# Vss.net
KiCad netlist of a schematic drawn in Altium Designer
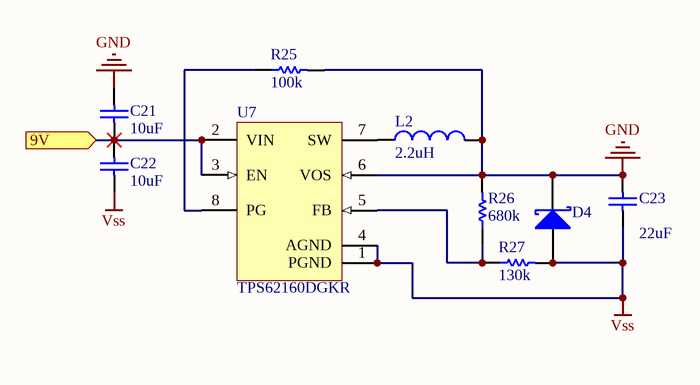
[diagram p0: Vss.SchDoc]

(export (version "E")
  (design (tool "Eeschema 10.0.6"))
  (components
    (comp (ref "C21")
      (value "10uF")
      (footprint "C1206")
      (description "Capacitor")
      (fields (field (name "Comment") "Cap") (field (name "PUBLISHER") "Altium Limited"))
      (libsource (lib "Miscellaneous Devices") (part "Cap"))
    )
    (comp (ref "C22")
      (value "10uF")
      (footprint "C1206")
      (description "Capacitor")
      (fields (field (name "Comment") "Cap") (field (name "PUBLISHER") "Altium Limited"))
      (libsource (lib "Miscellaneous Devices") (part "Cap"))
    )
    (comp (ref "C23")
      (value "22uF")
      (footprint "C1206")
      (description "Capacitor")
      (fields (field (name "Comment") "Cap") (field (name "PUBLISHER") "Altium Limited"))
      (libsource (lib "Miscellaneous Devices") (part "Cap"))
    )
    (comp (ref "D4")
      (value "D Schottky")
      (footprint "425")
      (description "Schottky Diode")
      (fields (field (name "PUBLISHER") "Altium Limited"))
      (libsource (lib "Miscellaneous Devices") (part "D Schottky"))
    )
    (comp (ref "L2")
      (value "2.2uH")
      (footprint "INDC1608L")
      (description "Inductor")
      (fields (field (name "PUBLISHER") "Altium Limited"))
      (libsource (lib "Miscellaneous Devices") (part "Inductor"))
    )
    (comp (ref "R25")
      (value "100k")
      (footprint "C1206")
      (description "Resistor")
      (fields (field (name "Comment") "Res1") (field (name "PUBLISHER") "Altium Limited"))
      (libsource (lib "Miscellaneous Devices") (part "Res1"))
    )
    (comp (ref "R26")
      (value "680k")
      (footprint "C1206")
      (description "Resistor")
      (fields (field (name "Comment") "Res1") (field (name "PUBLISHER") "Altium Limited"))
      (libsource (lib "Miscellaneous Devices") (part "Res1"))
    )
    (comp (ref "R27")
      (value "130k")
      (footprint "C1206")
      (description "Resistor")
      (fields (field (name "Comment") "Res1") (field (name "PUBLISHER") "Altium Limited"))
      (libsource (lib "Miscellaneous Devices") (part "Res1"))
    )
    (comp (ref "U7")
      (value "TPS62160DGKR")
      (footprint "DGK8_N")
      (fields (field (name "MANUFACTURER") "Texas Instruments"))
      (libsource (lib "TI Power Management Step-Down Regulator") (part "TPS62160DGKR"))
    )
  )
  (nets
    (net (code "1") (name "/9V") (class "Default")
      (node (ref "C21") (pin "1") (pinfunction "1_1") (pintype "passive"))
      (node (ref "C22") (pin "2") (pinfunction "2_2") (pintype "passive"))
      (node (ref "U7") (pin "2") (pinfunction "VIN_2") (pintype "power_in"))
      (node (ref "U7") (pin "3") (pinfunction "EN_3") (pintype "input"))
    )
    (net (code "2") (name "GND") (class "Default")
      (node (ref "C21") (pin "2") (pinfunction "2_2") (pintype "passive"))
      (node (ref "C23") (pin "2") (pinfunction "2_2") (pintype "passive"))
      (node (ref "D4") (pin "2") (pinfunction "K_2") (pintype "passive"))
      (node (ref "L2") (pin "2") (pinfunction "2_2") (pintype "passive"))
      (node (ref "R25") (pin "2") (pinfunction "2_2") (pintype "passive"))
      (node (ref "R26") (pin "2") (pinfunction "2_2") (pintype "passive"))
      (node (ref "U7") (pin "6") (pinfunction "VOS_6") (pintype "input"))
    )
    (net (code "3") (name "Net-(U7-FB)") (class "Default")
      (node (ref "R26") (pin "1") (pinfunction "1_1") (pintype "passive"))
      (node (ref "R27") (pin "1") (pinfunction "1_1") (pintype "passive"))
      (node (ref "U7") (pin "5") (pinfunction "FB_5") (pintype "input"))
    )
    (net (code "4") (name "Net-(U7-PG)") (class "Default")
      (node (ref "R25") (pin "1") (pinfunction "1_1") (pintype "passive"))
      (node (ref "U7") (pin "8") (pinfunction "PG_8") (pintype "tri_state"))
    )
    (net (code "5") (name "Net-(U7-SW)") (class "Default")
      (node (ref "L2") (pin "1") (pinfunction "1_1") (pintype "passive"))
      (node (ref "U7") (pin "7") (pinfunction "SW_7") (pintype "power_in"))
    )
    (net (code "6") (name "Vss") (class "Default")
      (node (ref "C22") (pin "1") (pinfunction "1_1") (pintype "passive"))
      (node (ref "C23") (pin "1") (pinfunction "1_1") (pintype "passive"))
      (node (ref "D4") (pin "1") (pinfunction "A_1") (pintype "passive"))
      (node (ref "R27") (pin "2") (pinfunction "2_2") (pintype "passive"))
      (node (ref "U7") (pin "1") (pinfunction "PGND_1") (pintype "power_in"))
      (node (ref "U7") (pin "4") (pinfunction "AGND_4") (pintype "power_in"))
    )
  )
)
